# OR_GATE.net
KiCad netlist of a schematic drawn in Altium Designer
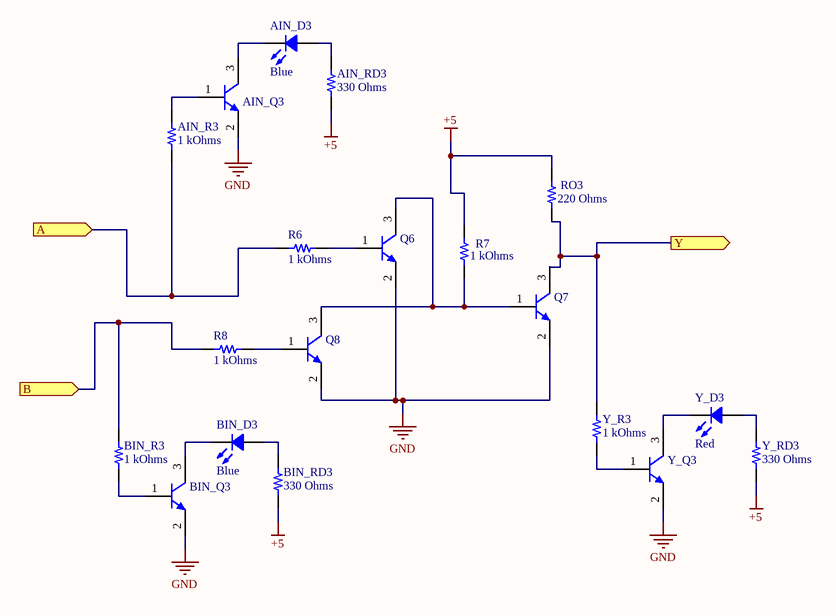
[diagram p0: OR_GATE.SchDoc]

(export (version "E")
  (design (tool "Eeschema 10.0.6"))
  (components
    (comp (ref "AIN_D3")
      (value "Blue")
      (footprint "LED 0603_1608 BLUE")
      (description "LED BLUE CLEAR 0603 SMD")
      (fields (field (name "PART NUMBER") "IN-S63AT5B") (field (name "MANUFACTURER") "Inolux"))
      (libsource (lib "Celestial Altium Library - altium_library") (part "LED"))
    )
    (comp (ref "AIN_Q3")
      (value "MMSS8050-L-TP")
      (footprint "MCCSEMI SOT-23-3")
      (description "TRANS NPN 25V 1.5A SOT23")
      (fields (field (name "MANUFACTURER") "Micro Commercial Co"))
      (libsource (lib "Celestial Altium Library - altium_library") (part "MCCSEMI NPN SOT-23-3"))
    )
    (comp (ref "AIN_R3")
      (value "1 kOhms")
      (footprint "RES 0603_1608")
      (description "RES SMD 1K OHM 0.1% 1/16W 0603")
      (fields
        (field (name "PART NUMBER") "CPF0603B1K0E")
        (field (name "MANUFACTURER") "TE Connectivity Passive Product")
      )
      (libsource (lib "Celestial Altium Library - altium_library") (part "Resistor"))
    )
    (comp (ref "AIN_RD3")
      (value "330 Ohms")
      (footprint "RES 0603_1608")
      (description "RES 330 OHM 5% 1/10W 0603")
      (fields
        (field (name "PART NUMBER") "RMCF0603JT330R")
        (field (name "MANUFACTURER") "Stackpole Electronics Inc")
      )
      (libsource (lib "Celestial Altium Library - altium_library") (part "Resistor"))
    )
    (comp (ref "BIN_D3")
      (value "Blue")
      (footprint "LED 0603_1608 BLUE")
      (description "LED BLUE CLEAR 0603 SMD")
      (fields (field (name "PART NUMBER") "IN-S63AT5B") (field (name "MANUFACTURER") "Inolux"))
      (libsource (lib "Celestial Altium Library - altium_library") (part "LED"))
    )
    (comp (ref "BIN_Q3")
      (value "MMSS8050-L-TP")
      (footprint "MCCSEMI SOT-23-3")
      (description "TRANS NPN 25V 1.5A SOT23")
      (fields (field (name "MANUFACTURER") "Micro Commercial Co"))
      (libsource (lib "Celestial Altium Library - altium_library") (part "MCCSEMI NPN SOT-23-3"))
    )
    (comp (ref "BIN_R3")
      (value "1 kOhms")
      (footprint "RES 0603_1608")
      (description "RES SMD 1K OHM 0.1% 1/16W 0603")
      (fields
        (field (name "PART NUMBER") "CPF0603B1K0E")
        (field (name "MANUFACTURER") "TE Connectivity Passive Product")
      )
      (libsource (lib "Celestial Altium Library - altium_library") (part "Resistor"))
    )
    (comp (ref "BIN_RD3")
      (value "330 Ohms")
      (footprint "RES 0603_1608")
      (description "RES 330 OHM 5% 1/10W 0603")
      (fields
        (field (name "PART NUMBER") "RMCF0603JT330R")
        (field (name "MANUFACTURER") "Stackpole Electronics Inc")
      )
      (libsource (lib "Celestial Altium Library - altium_library") (part "Resistor"))
    )
    (comp (ref "Q6")
      (value "MMSS8050-L-TP")
      (footprint "MCCSEMI SOT-23-3")
      (description "TRANS NPN 25V 1.5A SOT23")
      (fields (field (name "MANUFACTURER") "Micro Commercial Co"))
      (libsource (lib "Celestial Altium Library - altium_library") (part "MCCSEMI NPN SOT-23-3"))
    )
    (comp (ref "Q7")
      (value "MMSS8050-L-TP")
      (footprint "MCCSEMI SOT-23-3")
      (description "TRANS NPN 25V 1.5A SOT23")
      (fields (field (name "MANUFACTURER") "Micro Commercial Co"))
      (libsource (lib "Celestial Altium Library - altium_library") (part "MCCSEMI NPN SOT-23-3"))
    )
    (comp (ref "Q8")
      (value "MMSS8050-L-TP")
      (footprint "MCCSEMI SOT-23-3")
      (description "TRANS NPN 25V 1.5A SOT23")
      (fields (field (name "MANUFACTURER") "Micro Commercial Co"))
      (libsource (lib "Celestial Altium Library - altium_library") (part "MCCSEMI NPN SOT-23-3"))
    )
    (comp (ref "R6")
      (value "1 kOhms")
      (footprint "RES 0603_1608")
      (description "RES SMD 1K OHM 0.1% 1/16W 0603")
      (fields
        (field (name "PART NUMBER") "CPF0603B1K0E")
        (field (name "MANUFACTURER") "TE Connectivity Passive Product")
      )
      (libsource (lib "Celestial Altium Library - altium_library") (part "Resistor"))
    )
    (comp (ref "R7")
      (value "1 kOhms")
      (footprint "RES 0603_1608")
      (description "RES SMD 1K OHM 0.1% 1/16W 0603")
      (fields
        (field (name "PART NUMBER") "CPF0603B1K0E")
        (field (name "MANUFACTURER") "TE Connectivity Passive Product")
      )
      (libsource (lib "Celestial Altium Library - altium_library") (part "Resistor"))
    )
    (comp (ref "R8")
      (value "1 kOhms")
      (footprint "RES 0603_1608")
      (description "RES SMD 1K OHM 0.1% 1/16W 0603")
      (fields
        (field (name "PART NUMBER") "CPF0603B1K0E")
        (field (name "MANUFACTURER") "TE Connectivity Passive Product")
      )
      (libsource (lib "Celestial Altium Library - altium_library") (part "Resistor"))
    )
    (comp (ref "RO3")
      (value "220 Ohms")
      (footprint "RES 0603_1608")
      (description "RES SMD 220 OHM 0.5% 1/10W 0603")
      (fields
        (field (name "PART NUMBER") "ERA-3AED221V")
        (field (name "MANUFACTURER") "Panasonic Electronic Components")
      )
      (libsource (lib "Celestial Altium Library - altium_library") (part "Resistor"))
    )
    (comp (ref "Y_D3")
      (value "Red")
      (footprint "LED 0603_1608 RED")
      (description "LED RED CLEAR CHIP SMD")
      (fields (field (name "PART NUMBER") "XZMDK53W-8") (field (name "MANUFACTURER") "SunLED"))
      (libsource (lib "Celestial Altium Library - altium_library") (part "LED"))
    )
    (comp (ref "Y_Q3")
      (value "MMSS8050-L-TP")
      (footprint "MCCSEMI SOT-23-3")
      (description "TRANS NPN 25V 1.5A SOT23")
      (fields (field (name "MANUFACTURER") "Micro Commercial Co"))
      (libsource (lib "Celestial Altium Library - altium_library") (part "MCCSEMI NPN SOT-23-3"))
    )
    (comp (ref "Y_R3")
      (value "1 kOhms")
      (footprint "RES 0603_1608")
      (description "RES SMD 1K OHM 0.1% 1/16W 0603")
      (fields
        (field (name "PART NUMBER") "CPF0603B1K0E")
        (field (name "MANUFACTURER") "TE Connectivity Passive Product")
      )
      (libsource (lib "Celestial Altium Library - altium_library") (part "Resistor"))
    )
    (comp (ref "Y_RD3")
      (value "330 Ohms")
      (footprint "RES 0603_1608")
      (description "RES 330 OHM 5% 1/10W 0603")
      (fields
        (field (name "PART NUMBER") "RMCF0603JT330R")
        (field (name "MANUFACTURER") "Stackpole Electronics Inc")
      )
      (libsource (lib "Celestial Altium Library - altium_library") (part "Resistor"))
    )
  )
  (nets
    (net (code "1") (name "+5") (class "Default")
      (node (ref "AIN_RD3") (pin "1") (pinfunction "1_1") (pintype "passive"))
      (node (ref "BIN_RD3") (pin "1") (pinfunction "1_1") (pintype "passive"))
      (node (ref "R7") (pin "2") (pinfunction "2_2") (pintype "passive"))
      (node (ref "RO3") (pin "2") (pinfunction "2_2") (pintype "passive"))
      (node (ref "Y_RD3") (pin "1") (pinfunction "1_1") (pintype "passive"))
    )
    (net (code "2") (name "/A") (class "Default")
      (node (ref "AIN_R3") (pin "2") (pinfunction "2_2") (pintype "passive"))
      (node (ref "R6") (pin "1") (pinfunction "1_1") (pintype "passive"))
    )
    (net (code "3") (name "/B") (class "Default")
      (node (ref "BIN_R3") (pin "2") (pinfunction "2_2") (pintype "passive"))
      (node (ref "R8") (pin "1") (pinfunction "1_1") (pintype "passive"))
    )
    (net (code "4") (name "/Y") (class "Default")
      (node (ref "Q7") (pin "3") (pinfunction "C_3") (pintype "passive"))
      (node (ref "RO3") (pin "1") (pinfunction "1_1") (pintype "passive"))
      (node (ref "Y_R3") (pin "2") (pinfunction "2_2") (pintype "passive"))
    )
    (net (code "5") (name "GND") (class "Default")
      (node (ref "AIN_Q3") (pin "2") (pinfunction "E_2") (pintype "passive"))
      (node (ref "BIN_Q3") (pin "2") (pinfunction "E_2") (pintype "passive"))
      (node (ref "Q6") (pin "2") (pinfunction "E_2") (pintype "passive"))
      (node (ref "Q7") (pin "2") (pinfunction "E_2") (pintype "passive"))
      (node (ref "Q8") (pin "2") (pinfunction "E_2") (pintype "passive"))
      (node (ref "Y_Q3") (pin "2") (pinfunction "E_2") (pintype "passive"))
    )
    (net (code "6") (name "Net-(AIN_D3-Pad1)") (class "Default")
      (node (ref "AIN_D3") (pin "1") (pinfunction "1_1") (pintype "passive"))
      (node (ref "AIN_RD3") (pin "2") (pinfunction "2_2") (pintype "passive"))
    )
    (net (code "7") (name "Net-(AIN_Q3-B)") (class "Default")
      (node (ref "AIN_Q3") (pin "1") (pinfunction "B_1") (pintype "passive"))
      (node (ref "AIN_R3") (pin "1") (pinfunction "1_1") (pintype "passive"))
    )
    (net (code "8") (name "Net-(AIN_Q3-C)") (class "Default")
      (node (ref "AIN_D3") (pin "2") (pinfunction "2_2") (pintype "passive"))
      (node (ref "AIN_Q3") (pin "3") (pinfunction "C_3") (pintype "passive"))
    )
    (net (code "9") (name "Net-(BIN_D3-Pad1)") (class "Default")
      (node (ref "BIN_D3") (pin "1") (pinfunction "1_1") (pintype "passive"))
      (node (ref "BIN_RD3") (pin "2") (pinfunction "2_2") (pintype "passive"))
    )
    (net (code "10") (name "Net-(BIN_Q3-B)") (class "Default")
      (node (ref "BIN_Q3") (pin "1") (pinfunction "B_1") (pintype "passive"))
      (node (ref "BIN_R3") (pin "1") (pinfunction "1_1") (pintype "passive"))
    )
    (net (code "11") (name "Net-(BIN_Q3-C)") (class "Default")
      (node (ref "BIN_D3") (pin "2") (pinfunction "2_2") (pintype "passive"))
      (node (ref "BIN_Q3") (pin "3") (pinfunction "C_3") (pintype "passive"))
    )
    (net (code "12") (name "Net-(Q6-B)") (class "Default")
      (node (ref "Q6") (pin "1") (pinfunction "B_1") (pintype "passive"))
      (node (ref "R6") (pin "2") (pinfunction "2_2") (pintype "passive"))
    )
    (net (code "13") (name "Net-(Q6-C)") (class "Default")
      (node (ref "Q6") (pin "3") (pinfunction "C_3") (pintype "passive"))
      (node (ref "Q7") (pin "1") (pinfunction "B_1") (pintype "passive"))
      (node (ref "Q8") (pin "3") (pinfunction "C_3") (pintype "passive"))
      (node (ref "R7") (pin "1") (pinfunction "1_1") (pintype "passive"))
    )
    (net (code "14") (name "Net-(Q8-B)") (class "Default")
      (node (ref "Q8") (pin "1") (pinfunction "B_1") (pintype "passive"))
      (node (ref "R8") (pin "2") (pinfunction "2_2") (pintype "passive"))
    )
    (net (code "15") (name "Net-(Y_D3-Pad1)") (class "Default")
      (node (ref "Y_D3") (pin "1") (pinfunction "1_1") (pintype "passive"))
      (node (ref "Y_RD3") (pin "2") (pinfunction "2_2") (pintype "passive"))
    )
    (net (code "16") (name "Net-(Y_Q3-B)") (class "Default")
      (node (ref "Y_Q3") (pin "1") (pinfunction "B_1") (pintype "passive"))
      (node (ref "Y_R3") (pin "1") (pinfunction "1_1") (pintype "passive"))
    )
    (net (code "17") (name "Net-(Y_Q3-C)") (class "Default")
      (node (ref "Y_D3") (pin "2") (pinfunction "2_2") (pintype "passive"))
      (node (ref "Y_Q3") (pin "3") (pinfunction "C_3") (pintype "passive"))
    )
  )
)
